# SpannungsverdopplerMit3LED_1.net
KiCad netlist of a schematic drawn in EAGLE
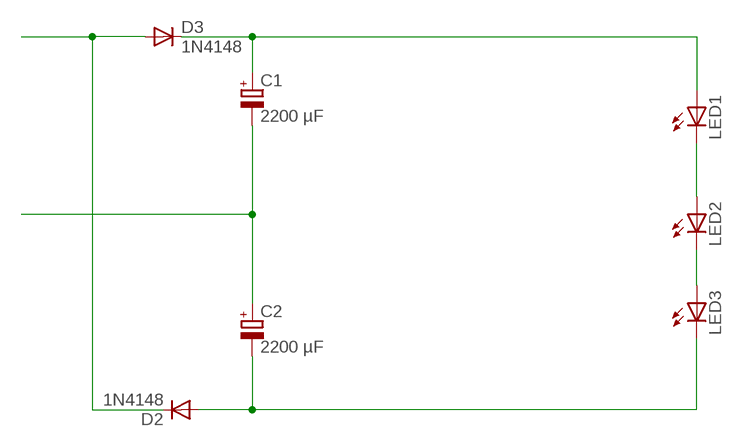
[diagram p0: schematic, sheet 1]

(export (version "E")
  (design (tool "Eeschema 10.0.6"))
  (components
    (comp (ref "C1")
      (value "2200 µF")
      (footprint "eagle-import:E5-10,5")
      (libsource (lib "eagle-import") (part "CPOL-EUE5-10.5"))
    )
    (comp (ref "C2")
      (value "2200 µF")
      (footprint "eagle-import:E5-10,5")
      (libsource (lib "eagle-import") (part "CPOL-EUE5-10.5"))
    )
    (comp (ref "D2")
      (value "1N4148")
      (footprint "eagle-import:DO35-10")
      (libsource (lib "eagle-import") (part "1N4148DO35-10"))
    )
    (comp (ref "D3")
      (value "1N4148")
      (footprint "eagle-import:DO35-10")
      (libsource (lib "eagle-import") (part "1N4148DO35-10"))
    )
    (comp (ref "LED1")
      (value "LED10MM")
      (footprint "eagle-import:LED10MM")
      (libsource (lib "eagle-import") (part "LED10MM"))
    )
    (comp (ref "LED2")
      (value "LED10MM")
      (footprint "eagle-import:LED10MM")
      (libsource (lib "eagle-import") (part "LED10MM"))
    )
    (comp (ref "LED3")
      (value "LED10MM")
      (footprint "eagle-import:LED10MM")
      (libsource (lib "eagle-import") (part "LED10MM"))
    )
  )
  (nets
    (net (code "1") (name "Net-(C1-Pad+)") (class "Default")
      (node (ref "C1") (pin "+") (pinfunction "+_+") (pintype "passive"))
      (node (ref "D3") (pin "C") (pinfunction "C_C") (pintype "passive"))
      (node (ref "LED1") (pin "A") (pinfunction "A_A") (pintype "passive"))
    )
    (net (code "2") (name "Net-(C1-Pad-)") (class "Default")
      (node (ref "C1") (pin "-") (pinfunction "-_-") (pintype "passive"))
      (node (ref "C2") (pin "+") (pinfunction "+_+") (pintype "passive"))
    )
    (net (code "3") (name "Net-(D2-PadC)") (class "Default")
      (node (ref "D2") (pin "C") (pinfunction "C_C") (pintype "passive"))
      (node (ref "D3") (pin "A") (pinfunction "A_A") (pintype "passive"))
    )
    (net (code "4") (name "Net-(LED1-C)") (class "Default")
      (node (ref "LED1") (pin "K") (pinfunction "C_K") (pintype "passive"))
      (node (ref "LED2") (pin "A") (pinfunction "A_A") (pintype "passive"))
    )
    (net (code "5") (name "Net-(LED2-C)") (class "Default")
      (node (ref "LED2") (pin "K") (pinfunction "C_K") (pintype "passive"))
      (node (ref "LED3") (pin "A") (pinfunction "A_A") (pintype "passive"))
    )
    (net (code "6") (name "Net-(LED3-C)") (class "Default")
      (node (ref "C2") (pin "-") (pinfunction "-_-") (pintype "passive"))
      (node (ref "D2") (pin "A") (pinfunction "A_A") (pintype "passive"))
      (node (ref "LED3") (pin "K") (pinfunction "C_K") (pintype "passive"))
    )
  )
)
